# micros.net
KiCad netlist of a schematic drawn in Altium Designer
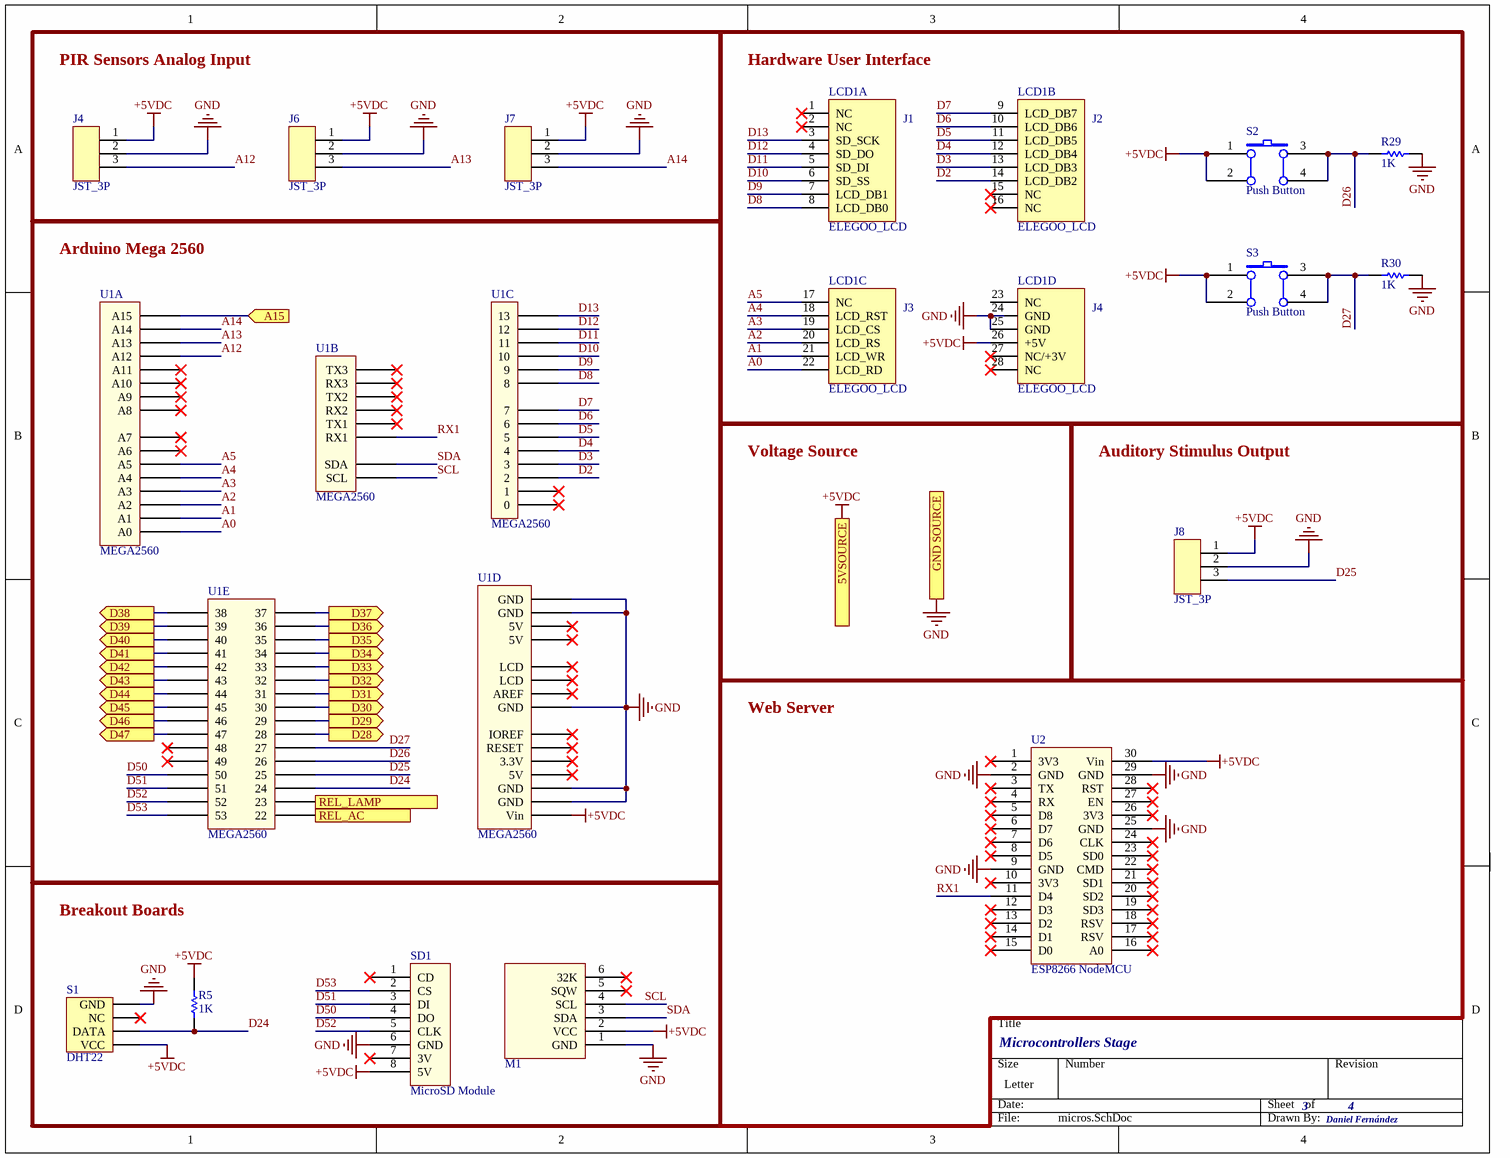
[diagram p0: micros.SchDoc]

(export (version "E")
  (design (tool "Eeschema 10.0.6"))
  (components
    (comp (ref "J4")
      (value "JST_3P")
      (footprint "JST_3P_ANGLE")
      (libsource (lib "Components_Schematics") (part "JST_3P"))
    )
    (comp (ref "J6")
      (value "JST_3P")
      (footprint "JST_3P_ANGLE")
      (libsource (lib "Components_Schematics") (part "JST_3P"))
    )
    (comp (ref "J7")
      (value "JST_3P")
      (footprint "JST_3P_ANGLE")
      (libsource (lib "Components_Schematics") (part "JST_3P"))
    )
    (comp (ref "J8")
      (value "JST_3P")
      (footprint "JST_3P_ANGLE")
      (libsource (lib "Components_Schematics") (part "JST_3P"))
    )
    (comp (ref "LCD1")
      (value "ELEGOO_LCD")
      (footprint "Elegoo_LCD")
      (description "LCD 2.8 in - 5 V")
      (fields (field (name "MANUFACTURER") "ELEGOO"))
      (libsource (lib "PERCRO_schematic") (part "ELEGOO_LCD_2.8"))
    )
    (comp (ref "M1")
      (value "DS3231")
      (footprint "DS3231_HORIZONTAL")
      (description "RTC MODULE")
      (libsource (lib "Components_Schematics") (part "DS3231"))
    )
    (comp (ref "R5")
      (value "1K")
      (footprint "RESISTOR")
      (description "Resistor_Axial")
      (fields (field (name "PUBLISHER") "Altium Limited"))
      (libsource (lib "PERCRO_schematic") (part "Resistor_Axial"))
    )
    (comp (ref "R29")
      (value "1K")
      (footprint "RESISTOR")
      (description "Resistor_Axial")
      (fields (field (name "PUBLISHER") "Altium Limited"))
      (libsource (lib "PERCRO_schematic") (part "Resistor_Axial"))
    )
    (comp (ref "R30")
      (value "1K")
      (footprint "RESISTOR")
      (description "Resistor_Axial")
      (fields (field (name "PUBLISHER") "Altium Limited"))
      (libsource (lib "PERCRO_schematic") (part "Resistor_Axial"))
    )
    (comp (ref "S1")
      (value "DHT22")
      (footprint "PERCRO_footprints:DHT22")
      (description "Sensor de humedad y temperatura")
      (fields (field (name "MANUFACTURER") "Aosong Electronics"))
      (libsource (lib "PERCRO_schematic") (part "DHT22"))
    )
    (comp (ref "S2")
      (value "Push Button")
      (footprint "PUSH_BUTTON")
      (libsource (lib "Components_Schematics") (part "Push_Button_4Pin"))
    )
    (comp (ref "S3")
      (value "Push Button")
      (footprint "PUSH_BUTTON")
      (libsource (lib "Components_Schematics") (part "Push_Button_4Pin"))
    )
    (comp (ref "SD1")
      (value "MicroSD Module")
      (footprint "Micro-SD")
      (description "Adafruit Micro SD Card Breakout Board")
      (libsource (lib "Components_Schematics") (part "Micro-SD"))
    )
    (comp (ref "U1")
      (value "MEGA2560")
      (footprint "MEGA2560_Inv")
      (description "Arduino Mega2560")
      (libsource (lib "Components_Schematics") (part "MEGA2560"))
    )
    (comp (ref "U2")
      (value "ESP8266 NodeMCU")
      (footprint "ESP8266_NodeMCU")
      (description "NODEMCU V2 ESP8266")
      (libsource (lib "Components_Schematics") (part "ESP8266"))
    )
  )
  (nets
    (net (code "1") (name "+5VDC") (class "Default")
      (node (ref "J4") (pin "1") (pinfunction "1_1") (pintype "passive"))
      (node (ref "J6") (pin "1") (pinfunction "1_1") (pintype "passive"))
      (node (ref "J7") (pin "1") (pinfunction "1_1") (pintype "passive"))
      (node (ref "J8") (pin "1") (pinfunction "1_1") (pintype "passive"))
      (node (ref "LCD1") (pin "26") (pinfunction "+5V_26") (pintype "passive"))
      (node (ref "M1") (pin "2") (pinfunction "VCC_2") (pintype "passive"))
      (node (ref "R5") (pin "1") (pinfunction "1_1") (pintype "passive"))
      (node (ref "S1") (pin "1") (pinfunction "VCC_1") (pintype "passive"))
      (node (ref "S2") (pin "1") (pinfunction "1_1") (pintype "passive"))
      (node (ref "S2") (pin "2") (pinfunction "2_2") (pintype "passive"))
      (node (ref "S3") (pin "1") (pinfunction "1_1") (pintype "passive"))
      (node (ref "S3") (pin "2") (pinfunction "2_2") (pintype "passive"))
      (node (ref "SD1") (pin "8") (pinfunction "5V_8") (pintype "passive"))
      (node (ref "U1") (pin "Vin") (pinfunction "Vin_Vin") (pintype "passive"))
      (node (ref "U2") (pin "30") (pinfunction "Vin_30") (pintype "passive"))
    )
    (net (code "2") (name "/A0") (class "Default")
      (node (ref "LCD1") (pin "22") (pinfunction "LCD_RD_22") (pintype "passive"))
      (node (ref "U1") (pin "A0") (pinfunction "A0_A0") (pintype "passive"))
    )
    (net (code "3") (name "/A1") (class "Default")
      (node (ref "LCD1") (pin "21") (pinfunction "LCD_WR_21") (pintype "passive"))
      (node (ref "U1") (pin "A1") (pinfunction "A1_A1") (pintype "passive"))
    )
    (net (code "4") (name "/A2") (class "Default")
      (node (ref "LCD1") (pin "20") (pinfunction "LCD_RS_20") (pintype "passive"))
      (node (ref "U1") (pin "A2") (pinfunction "A2_A2") (pintype "passive"))
    )
    (net (code "5") (name "/A3") (class "Default")
      (node (ref "LCD1") (pin "19") (pinfunction "LCD_CS_19") (pintype "passive"))
      (node (ref "U1") (pin "A3") (pinfunction "A3_A3") (pintype "passive"))
    )
    (net (code "6") (name "/A4") (class "Default")
      (node (ref "LCD1") (pin "18") (pinfunction "LCD_RST_18") (pintype "passive"))
      (node (ref "U1") (pin "A4") (pinfunction "A4_A4") (pintype "passive"))
    )
    (net (code "7") (name "/A5") (class "Default")
      (node (ref "LCD1") (pin "17") (pinfunction "NC_17") (pintype "passive"))
      (node (ref "U1") (pin "A5") (pinfunction "A5_A5") (pintype "passive"))
    )
    (net (code "8") (name "/A12") (class "Default")
      (node (ref "J4") (pin "3") (pinfunction "3_3") (pintype "passive"))
      (node (ref "U1") (pin "A12") (pinfunction "A12_A12") (pintype "passive"))
    )
    (net (code "9") (name "/A13") (class "Default")
      (node (ref "J6") (pin "3") (pinfunction "3_3") (pintype "passive"))
      (node (ref "U1") (pin "A13") (pinfunction "A13_A13") (pintype "passive"))
    )
    (net (code "10") (name "/A14") (class "Default")
      (node (ref "J7") (pin "3") (pinfunction "3_3") (pintype "passive"))
      (node (ref "U1") (pin "A14") (pinfunction "A14_A14") (pintype "passive"))
    )
    (net (code "11") (name "/A15") (class "Default")
      (node (ref "U1") (pin "A15") (pinfunction "A15_A15") (pintype "passive"))
    )
    (net (code "12") (name "/D2") (class "Default")
      (node (ref "LCD1") (pin "14") (pinfunction "LCD_DB2_14") (pintype "passive"))
      (node (ref "U1") (pin "2") (pinfunction "2_2") (pintype "passive"))
    )
    (net (code "13") (name "/D3") (class "Default")
      (node (ref "LCD1") (pin "13") (pinfunction "LCD_DB3_13") (pintype "passive"))
      (node (ref "U1") (pin "3") (pinfunction "3_3") (pintype "passive"))
    )
    (net (code "14") (name "/D4") (class "Default")
      (node (ref "LCD1") (pin "12") (pinfunction "LCD_DB4_12") (pintype "passive"))
      (node (ref "U1") (pin "4") (pinfunction "4_4") (pintype "passive"))
    )
    (net (code "15") (name "/D5") (class "Default")
      (node (ref "LCD1") (pin "11") (pinfunction "LCD_DB5_11") (pintype "passive"))
      (node (ref "U1") (pin "5") (pinfunction "5_5") (pintype "passive"))
    )
    (net (code "16") (name "/D6") (class "Default")
      (node (ref "LCD1") (pin "10") (pinfunction "LCD_DB6_10") (pintype "passive"))
      (node (ref "U1") (pin "6") (pinfunction "6_6") (pintype "passive"))
    )
    (net (code "17") (name "/D7") (class "Default")
      (node (ref "LCD1") (pin "9") (pinfunction "LCD_DB7_9") (pintype "passive"))
      (node (ref "U1") (pin "7") (pinfunction "7_7") (pintype "passive"))
    )
    (net (code "18") (name "/D8") (class "Default")
      (node (ref "LCD1") (pin "8") (pinfunction "LCD_DB0_8") (pintype "passive"))
      (node (ref "U1") (pin "8") (pinfunction "8_8") (pintype "passive"))
    )
    (net (code "19") (name "/D9") (class "Default")
      (node (ref "LCD1") (pin "7") (pinfunction "LCD_DB1_7") (pintype "passive"))
      (node (ref "U1") (pin "9") (pinfunction "9_9") (pintype "passive"))
    )
    (net (code "20") (name "/D10") (class "Default")
      (node (ref "LCD1") (pin "6") (pinfunction "SD_SS_6") (pintype "passive"))
      (node (ref "U1") (pin "10") (pinfunction "10_10") (pintype "passive"))
    )
    (net (code "21") (name "/D11") (class "Default")
      (node (ref "LCD1") (pin "5") (pinfunction "SD_DI_5") (pintype "passive"))
      (node (ref "U1") (pin "11") (pinfunction "11_11") (pintype "passive"))
    )
    (net (code "22") (name "/D12") (class "Default")
      (node (ref "LCD1") (pin "4") (pinfunction "SD_DO_4") (pintype "passive"))
      (node (ref "U1") (pin "12") (pinfunction "12_12") (pintype "passive"))
    )
    (net (code "23") (name "/D13") (class "Default")
      (node (ref "LCD1") (pin "3") (pinfunction "SD_SCK_3") (pintype "passive"))
      (node (ref "U1") (pin "13") (pinfunction "13_13") (pintype "passive"))
    )
    (net (code "24") (name "/D24") (class "Default")
      (node (ref "R5") (pin "2") (pinfunction "2_2") (pintype "passive"))
      (node (ref "S1") (pin "2") (pinfunction "DATA_2") (pintype "passive"))
      (node (ref "U1") (pin "24") (pinfunction "24_24") (pintype "passive"))
    )
    (net (code "25") (name "/D25") (class "Default")
      (node (ref "J8") (pin "3") (pinfunction "3_3") (pintype "passive"))
      (node (ref "U1") (pin "25") (pinfunction "25_25") (pintype "passive"))
    )
    (net (code "26") (name "/D26") (class "Default")
      (node (ref "R29") (pin "1") (pinfunction "1_1") (pintype "passive"))
      (node (ref "S2") (pin "3") (pinfunction "3_3") (pintype "passive"))
      (node (ref "S2") (pin "4") (pinfunction "4_4") (pintype "passive"))
      (node (ref "U1") (pin "26") (pinfunction "26_26") (pintype "passive"))
    )
    (net (code "27") (name "/D27") (class "Default")
      (node (ref "R30") (pin "1") (pinfunction "1_1") (pintype "passive"))
      (node (ref "S3") (pin "3") (pinfunction "3_3") (pintype "passive"))
      (node (ref "S3") (pin "4") (pinfunction "4_4") (pintype "passive"))
      (node (ref "U1") (pin "27") (pinfunction "27_27") (pintype "passive"))
    )
    (net (code "28") (name "/D28") (class "Default")
      (node (ref "U1") (pin "28") (pinfunction "28_28") (pintype "passive"))
    )
    (net (code "29") (name "/D29") (class "Default")
      (node (ref "U1") (pin "29") (pinfunction "29_29") (pintype "passive"))
    )
    (net (code "30") (name "/D30") (class "Default")
      (node (ref "U1") (pin "30") (pinfunction "30_30") (pintype "passive"))
    )
    (net (code "31") (name "/D31") (class "Default")
      (node (ref "U1") (pin "31") (pinfunction "31_31") (pintype "passive"))
    )
    (net (code "32") (name "/D32") (class "Default")
      (node (ref "U1") (pin "32") (pinfunction "32_32") (pintype "passive"))
    )
    (net (code "33") (name "/D33") (class "Default")
      (node (ref "U1") (pin "33") (pinfunction "33_33") (pintype "passive"))
    )
    (net (code "34") (name "/D34") (class "Default")
      (node (ref "U1") (pin "34") (pinfunction "34_34") (pintype "passive"))
    )
    (net (code "35") (name "/D35") (class "Default")
      (node (ref "U1") (pin "35") (pinfunction "35_35") (pintype "passive"))
    )
    (net (code "36") (name "/D36") (class "Default")
      (node (ref "U1") (pin "36") (pinfunction "36_36") (pintype "passive"))
    )
    (net (code "37") (name "/D37") (class "Default")
      (node (ref "U1") (pin "37") (pinfunction "37_37") (pintype "passive"))
    )
    (net (code "38") (name "/D38") (class "Default")
      (node (ref "U1") (pin "38") (pinfunction "38_38") (pintype "passive"))
    )
    (net (code "39") (name "/D39") (class "Default")
      (node (ref "U1") (pin "39") (pinfunction "39_39") (pintype "passive"))
    )
    (net (code "40") (name "/D40") (class "Default")
      (node (ref "U1") (pin "40") (pinfunction "40_40") (pintype "passive"))
    )
    (net (code "41") (name "/D41") (class "Default")
      (node (ref "U1") (pin "41") (pinfunction "41_41") (pintype "passive"))
    )
    (net (code "42") (name "/D42") (class "Default")
      (node (ref "U1") (pin "42") (pinfunction "42_42") (pintype "passive"))
    )
    (net (code "43") (name "/D43") (class "Default")
      (node (ref "U1") (pin "43") (pinfunction "43_43") (pintype "passive"))
    )
    (net (code "44") (name "/D44") (class "Default")
      (node (ref "U1") (pin "44") (pinfunction "44_44") (pintype "passive"))
    )
    (net (code "45") (name "/D45") (class "Default")
      (node (ref "U1") (pin "45") (pinfunction "45_45") (pintype "passive"))
    )
    (net (code "46") (name "/D46") (class "Default")
      (node (ref "U1") (pin "46") (pinfunction "46_46") (pintype "passive"))
    )
    (net (code "47") (name "/D47") (class "Default")
      (node (ref "U1") (pin "47") (pinfunction "47_47") (pintype "passive"))
    )
    (net (code "48") (name "/D50") (class "Default")
      (node (ref "SD1") (pin "4") (pinfunction "DO_4") (pintype "passive"))
      (node (ref "U1") (pin "50") (pinfunction "50_50") (pintype "passive"))
    )
    (net (code "49") (name "/D51") (class "Default")
      (node (ref "SD1") (pin "3") (pinfunction "DI_3") (pintype "passive"))
      (node (ref "U1") (pin "51") (pinfunction "51_51") (pintype "passive"))
    )
    (net (code "50") (name "/D52") (class "Default")
      (node (ref "SD1") (pin "5") (pinfunction "CLK_5") (pintype "passive"))
      (node (ref "U1") (pin "52") (pinfunction "52_52") (pintype "passive"))
    )
    (net (code "51") (name "/D53") (class "Default")
      (node (ref "SD1") (pin "2") (pinfunction "CS_2") (pintype "passive"))
      (node (ref "U1") (pin "53") (pinfunction "53_53") (pintype "passive"))
    )
    (net (code "52") (name "/REL_AC") (class "Default")
      (node (ref "U1") (pin "22") (pinfunction "22_22") (pintype "passive"))
    )
    (net (code "53") (name "/REL_LAMP") (class "Default")
      (node (ref "U1") (pin "23") (pinfunction "23_23") (pintype "passive"))
    )
    (net (code "54") (name "/RX1") (class "Default")
      (node (ref "U1") (pin "RX1") (pinfunction "RX1_RX1") (pintype "passive"))
      (node (ref "U2") (pin "11") (pinfunction "D4_11") (pintype "passive"))
    )
    (net (code "55") (name "/SCL") (class "Default")
      (node (ref "M1") (pin "4") (pinfunction "SCL_4") (pintype "passive"))
      (node (ref "U1") (pin "SCL") (pinfunction "SCL_SCL") (pintype "passive"))
    )
    (net (code "56") (name "/SDA") (class "Default")
      (node (ref "M1") (pin "3") (pinfunction "SDA_3") (pintype "passive"))
      (node (ref "U1") (pin "SDA") (pinfunction "SDA_SDA") (pintype "passive"))
    )
    (net (code "57") (name "GND") (class "Default")
      (node (ref "J4") (pin "2") (pinfunction "2_2") (pintype "passive"))
      (node (ref "J6") (pin "2") (pinfunction "2_2") (pintype "passive"))
      (node (ref "J7") (pin "2") (pinfunction "2_2") (pintype "passive"))
      (node (ref "J8") (pin "2") (pinfunction "2_2") (pintype "passive"))
      (node (ref "LCD1") (pin "24") (pinfunction "GND_24") (pintype "passive"))
      (node (ref "LCD1") (pin "25") (pinfunction "GND_25") (pintype "passive"))
      (node (ref "M1") (pin "1") (pinfunction "GND_1") (pintype "passive"))
      (node (ref "R29") (pin "2") (pinfunction "2_2") (pintype "passive"))
      (node (ref "R30") (pin "2") (pinfunction "2_2") (pintype "passive"))
      (node (ref "S1") (pin "4") (pinfunction "GND_4") (pintype "passive"))
      (node (ref "SD1") (pin "6") (pinfunction "GND_6") (pintype "passive"))
      (node (ref "U1") (pin "GND") (pinfunction "GND_GND") (pintype "passive"))
      (node (ref "U1") (pin "GND_1") (pinfunction "GND_GND_1") (pintype "passive"))
      (node (ref "U1") (pin "GND_2") (pinfunction "GND_GND_2") (pintype "passive"))
      (node (ref "U1") (pin "GND_3") (pinfunction "GND_GND_3") (pintype "passive"))
      (node (ref "U1") (pin "GND_4") (pinfunction "GND_GND_4") (pintype "passive"))
      (node (ref "U2") (pin "2") (pinfunction "GND_2") (pintype "passive"))
      (node (ref "U2") (pin "25") (pinfunction "GND_25") (pintype "passive"))
      (node (ref "U2") (pin "29") (pinfunction "GND_29") (pintype "passive"))
      (node (ref "U2") (pin "9") (pinfunction "GND_9") (pintype "passive"))
    )
    (net (code "58") (name "unconnected-(LCD1A-NC-Pad1)") (class "Default")
      (node (ref "LCD1") (pin "1") (pinfunction "NC_1") (pintype "passive+no_connect"))
    )
    (net (code "59") (name "unconnected-(LCD1A-NC-Pad2)") (class "Default")
      (node (ref "LCD1") (pin "2") (pinfunction "NC_2") (pintype "passive+no_connect"))
    )
    (net (code "60") (name "unconnected-(LCD1B-NC-Pad15)") (class "Default")
      (node (ref "LCD1") (pin "15") (pinfunction "NC_15") (pintype "passive+no_connect"))
    )
    (net (code "61") (name "unconnected-(LCD1B-NC-Pad16)") (class "Default")
      (node (ref "LCD1") (pin "16") (pinfunction "NC_16") (pintype "passive+no_connect"))
    )
    (net (code "62") (name "unconnected-(LCD1D-NC-Pad23)") (class "Default")
      (node (ref "LCD1") (pin "23") (pinfunction "NC_23") (pintype "passive"))
    )
    (net (code "63") (name "unconnected-(LCD1D-NC-Pad28)") (class "Default")
      (node (ref "LCD1") (pin "28") (pinfunction "NC_28") (pintype "passive+no_connect"))
    )
    (net (code "64") (name "unconnected-(LCD1D-NC{slash}+3V-Pad27)") (class "Default")
      (node (ref "LCD1") (pin "27") (pinfunction "NC/+3V_27") (pintype "passive+no_connect"))
    )
    (net (code "65") (name "unconnected-(M1-32K-Pad6)") (class "Default")
      (node (ref "M1") (pin "6") (pinfunction "32K_6") (pintype "passive+no_connect"))
    )
    (net (code "66") (name "unconnected-(M1-SQW-Pad5)") (class "Default")
      (node (ref "M1") (pin "5") (pinfunction "SQW_5") (pintype "passive+no_connect"))
    )
    (net (code "67") (name "unconnected-(S1-NC-Pad3)") (class "Default")
      (node (ref "S1") (pin "3") (pinfunction "NC_3") (pintype "passive+no_connect"))
    )
    (net (code "68") (name "unconnected-(SD1-3V-Pad7)") (class "Default")
      (node (ref "SD1") (pin "7") (pinfunction "3V_7") (pintype "passive+no_connect"))
    )
    (net (code "69") (name "unconnected-(SD1-CD-Pad1)") (class "Default")
      (node (ref "SD1") (pin "1") (pinfunction "CD_1") (pintype "passive+no_connect"))
    )
    (net (code "70") (name "unconnected-(U1-Pad0)") (class "Default")
      (node (ref "U1") (pin "0") (pinfunction "0_0") (pintype "passive+no_connect"))
    )
    (net (code "71") (name "unconnected-(U1-Pad1)") (class "Default")
      (node (ref "U1") (pin "1") (pinfunction "1_1") (pintype "passive+no_connect"))
    )
    (net (code "72") (name "unconnected-(U1-Pad3.3V)") (class "Default")
      (node (ref "U1") (pin "3.3V") (pinfunction "3.3V_3.3V") (pintype "passive+no_connect"))
    )
    (net (code "73") (name "unconnected-(U1-Pad5V)") (class "Default")
      (node (ref "U1") (pin "5V") (pinfunction "5V_5V") (pintype "passive+no_connect"))
    )
    (net (code "74") (name "unconnected-(U1-Pad48)") (class "Default")
      (node (ref "U1") (pin "48") (pinfunction "48_48") (pintype "passive+no_connect"))
    )
    (net (code "75") (name "unconnected-(U1-Pad49)") (class "Default")
      (node (ref "U1") (pin "49") (pinfunction "49_49") (pintype "passive+no_connect"))
    )
    (net (code "76") (name "unconnected-(U1-PadA6)") (class "Default")
      (node (ref "U1") (pin "A6") (pinfunction "A6_A6") (pintype "passive+no_connect"))
    )
    (net (code "77") (name "unconnected-(U1-PadA7)") (class "Default")
      (node (ref "U1") (pin "A7") (pinfunction "A7_A7") (pintype "passive+no_connect"))
    )
    (net (code "78") (name "unconnected-(U1-PadA8)") (class "Default")
      (node (ref "U1") (pin "A8") (pinfunction "A8_A8") (pintype "passive+no_connect"))
    )
    (net (code "79") (name "unconnected-(U1-PadA9)") (class "Default")
      (node (ref "U1") (pin "A9") (pinfunction "A9_A9") (pintype "passive+no_connect"))
    )
    (net (code "80") (name "unconnected-(U1-PadA10)") (class "Default")
      (node (ref "U1") (pin "A10") (pinfunction "A10_A10") (pintype "passive+no_connect"))
    )
    (net (code "81") (name "unconnected-(U1-PadA11)") (class "Default")
      (node (ref "U1") (pin "A11") (pinfunction "A11_A11") (pintype "passive+no_connect"))
    )
    (net (code "82") (name "unconnected-(U1-PadAREF)") (class "Default")
      (node (ref "U1") (pin "AREF") (pinfunction "AREF_AREF") (pintype "passive+no_connect"))
    )
    (net (code "83") (name "unconnected-(U1-PadIOREF)") (class "Default")
      (node (ref "U1") (pin "IOREF") (pinfunction "IOREF_IOREF") (pintype "passive+no_connect"))
    )
    (net (code "84") (name "unconnected-(U1-PadLCD)") (class "Default")
      (node (ref "U1") (pin "LCD") (pinfunction "LCD_LCD") (pintype "passive+no_connect"))
    )
    (net (code "85") (name "unconnected-(U1-PadRESET)") (class "Default")
      (node (ref "U1") (pin "RESET") (pinfunction "RESET_RESET") (pintype "passive+no_connect"))
    )
    (net (code "86") (name "unconnected-(U1-PadRX2)") (class "Default")
      (node (ref "U1") (pin "RX2") (pinfunction "RX2_RX2") (pintype "passive+no_connect"))
    )
    (net (code "87") (name "unconnected-(U1-PadRX3)") (class "Default")
      (node (ref "U1") (pin "RX3") (pinfunction "RX3_RX3") (pintype "passive+no_connect"))
    )
    (net (code "88") (name "unconnected-(U1-PadTX1)") (class "Default")
      (node (ref "U1") (pin "TX1") (pinfunction "TX1_TX1") (pintype "passive+no_connect"))
    )
    (net (code "89") (name "unconnected-(U1-PadTX2)") (class "Default")
      (node (ref "U1") (pin "TX2") (pinfunction "TX2_TX2") (pintype "passive+no_connect"))
    )
    (net (code "90") (name "unconnected-(U1-PadTX3)") (class "Default")
      (node (ref "U1") (pin "TX3") (pinfunction "TX3_TX3") (pintype "passive+no_connect"))
    )
    (net (code "91") (name "unconnected-(U1D-5V-Pad5V_1)") (class "Default")
      (node (ref "U1") (pin "5V_1") (pinfunction "5V_5V_1") (pintype "passive+no_connect"))
    )
    (net (code "92") (name "unconnected-(U1D-5V-Pad5V_2)") (class "Default")
      (node (ref "U1") (pin "5V_2") (pinfunction "5V_5V_2") (pintype "passive+no_connect"))
    )
    (net (code "93") (name "unconnected-(U1D-LCD-PadLCD_1)") (class "Default")
      (node (ref "U1") (pin "LCD_1") (pinfunction "LCD_LCD_1") (pintype "passive+no_connect"))
    )
    (net (code "94") (name "unconnected-(U2-3V3-Pad1)") (class "Default")
      (node (ref "U2") (pin "1") (pinfunction "3V3_1") (pintype "passive+no_connect"))
    )
    (net (code "95") (name "unconnected-(U2-3V3-Pad10)") (class "Default")
      (node (ref "U2") (pin "10") (pinfunction "3V3_10") (pintype "passive+no_connect"))
    )
    (net (code "96") (name "unconnected-(U2-3V3-Pad26)") (class "Default")
      (node (ref "U2") (pin "26") (pinfunction "3V3_26") (pintype "passive+no_connect"))
    )
    (net (code "97") (name "unconnected-(U2-A0-Pad16)") (class "Default")
      (node (ref "U2") (pin "16") (pinfunction "A0_16") (pintype "passive+no_connect"))
    )
    (net (code "98") (name "unconnected-(U2-CLK-Pad24)") (class "Default")
      (node (ref "U2") (pin "24") (pinfunction "CLK_24") (pintype "passive+no_connect"))
    )
    (net (code "99") (name "unconnected-(U2-CMD-Pad22)") (class "Default")
      (node (ref "U2") (pin "22") (pinfunction "CMD_22") (pintype "passive+no_connect"))
    )
    (net (code "100") (name "unconnected-(U2-D0-Pad15)") (class "Default")
      (node (ref "U2") (pin "15") (pinfunction "D0_15") (pintype "passive+no_connect"))
    )
    (net (code "101") (name "unconnected-(U2-D1-Pad14)") (class "Default")
      (node (ref "U2") (pin "14") (pinfunction "D1_14") (pintype "passive+no_connect"))
    )
    (net (code "102") (name "unconnected-(U2-D2-Pad13)") (class "Default")
      (node (ref "U2") (pin "13") (pinfunction "D2_13") (pintype "passive+no_connect"))
    )
    (net (code "103") (name "unconnected-(U2-D3-Pad12)") (class "Default")
      (node (ref "U2") (pin "12") (pinfunction "D3_12") (pintype "passive+no_connect"))
    )
    (net (code "104") (name "unconnected-(U2-D5-Pad8)") (class "Default")
      (node (ref "U2") (pin "8") (pinfunction "D5_8") (pintype "passive+no_connect"))
    )
    (net (code "105") (name "unconnected-(U2-D6-Pad7)") (class "Default")
      (node (ref "U2") (pin "7") (pinfunction "D6_7") (pintype "passive+no_connect"))
    )
    (net (code "106") (name "unconnected-(U2-D7-Pad6)") (class "Default")
      (node (ref "U2") (pin "6") (pinfunction "D7_6") (pintype "passive+no_connect"))
    )
    (net (code "107") (name "unconnected-(U2-D8-Pad5)") (class "Default")
      (node (ref "U2") (pin "5") (pinfunction "D8_5") (pintype "passive+no_connect"))
    )
    (net (code "108") (name "unconnected-(U2-EN-Pad27)") (class "Default")
      (node (ref "U2") (pin "27") (pinfunction "EN_27") (pintype "passive+no_connect"))
    )
    (net (code "109") (name "unconnected-(U2-RST-Pad28)") (class "Default")
      (node (ref "U2") (pin "28") (pinfunction "RST_28") (pintype "passive+no_connect"))
    )
    (net (code "110") (name "unconnected-(U2-RSV-Pad17)") (class "Default")
      (node (ref "U2") (pin "17") (pinfunction "RSV_17") (pintype "passive+no_connect"))
    )
    (net (code "111") (name "unconnected-(U2-RSV-Pad18)") (class "Default")
      (node (ref "U2") (pin "18") (pinfunction "RSV_18") (pintype "passive+no_connect"))
    )
    (net (code "112") (name "unconnected-(U2-RX-Pad4)") (class "Default")
      (node (ref "U2") (pin "4") (pinfunction "RX_4") (pintype "passive+no_connect"))
    )
    (net (code "113") (name "unconnected-(U2-SD0-Pad23)") (class "Default")
      (node (ref "U2") (pin "23") (pinfunction "SD0_23") (pintype "passive+no_connect"))
    )
    (net (code "114") (name "unconnected-(U2-SD1-Pad21)") (class "Default")
      (node (ref "U2") (pin "21") (pinfunction "SD1_21") (pintype "passive+no_connect"))
    )
    (net (code "115") (name "unconnected-(U2-SD2-Pad20)") (class "Default")
      (node (ref "U2") (pin "20") (pinfunction "SD2_20") (pintype "passive+no_connect"))
    )
    (net (code "116") (name "unconnected-(U2-SD3-Pad19)") (class "Default")
      (node (ref "U2") (pin "19") (pinfunction "SD3_19") (pintype "passive+no_connect"))
    )
    (net (code "117") (name "unconnected-(U2-TX-Pad3)") (class "Default")
      (node (ref "U2") (pin "3") (pinfunction "TX_3") (pintype "passive+no_connect"))
    )
  )
)
